# PR9021.net
KiCad netlist of a schematic drawn in EAGLE
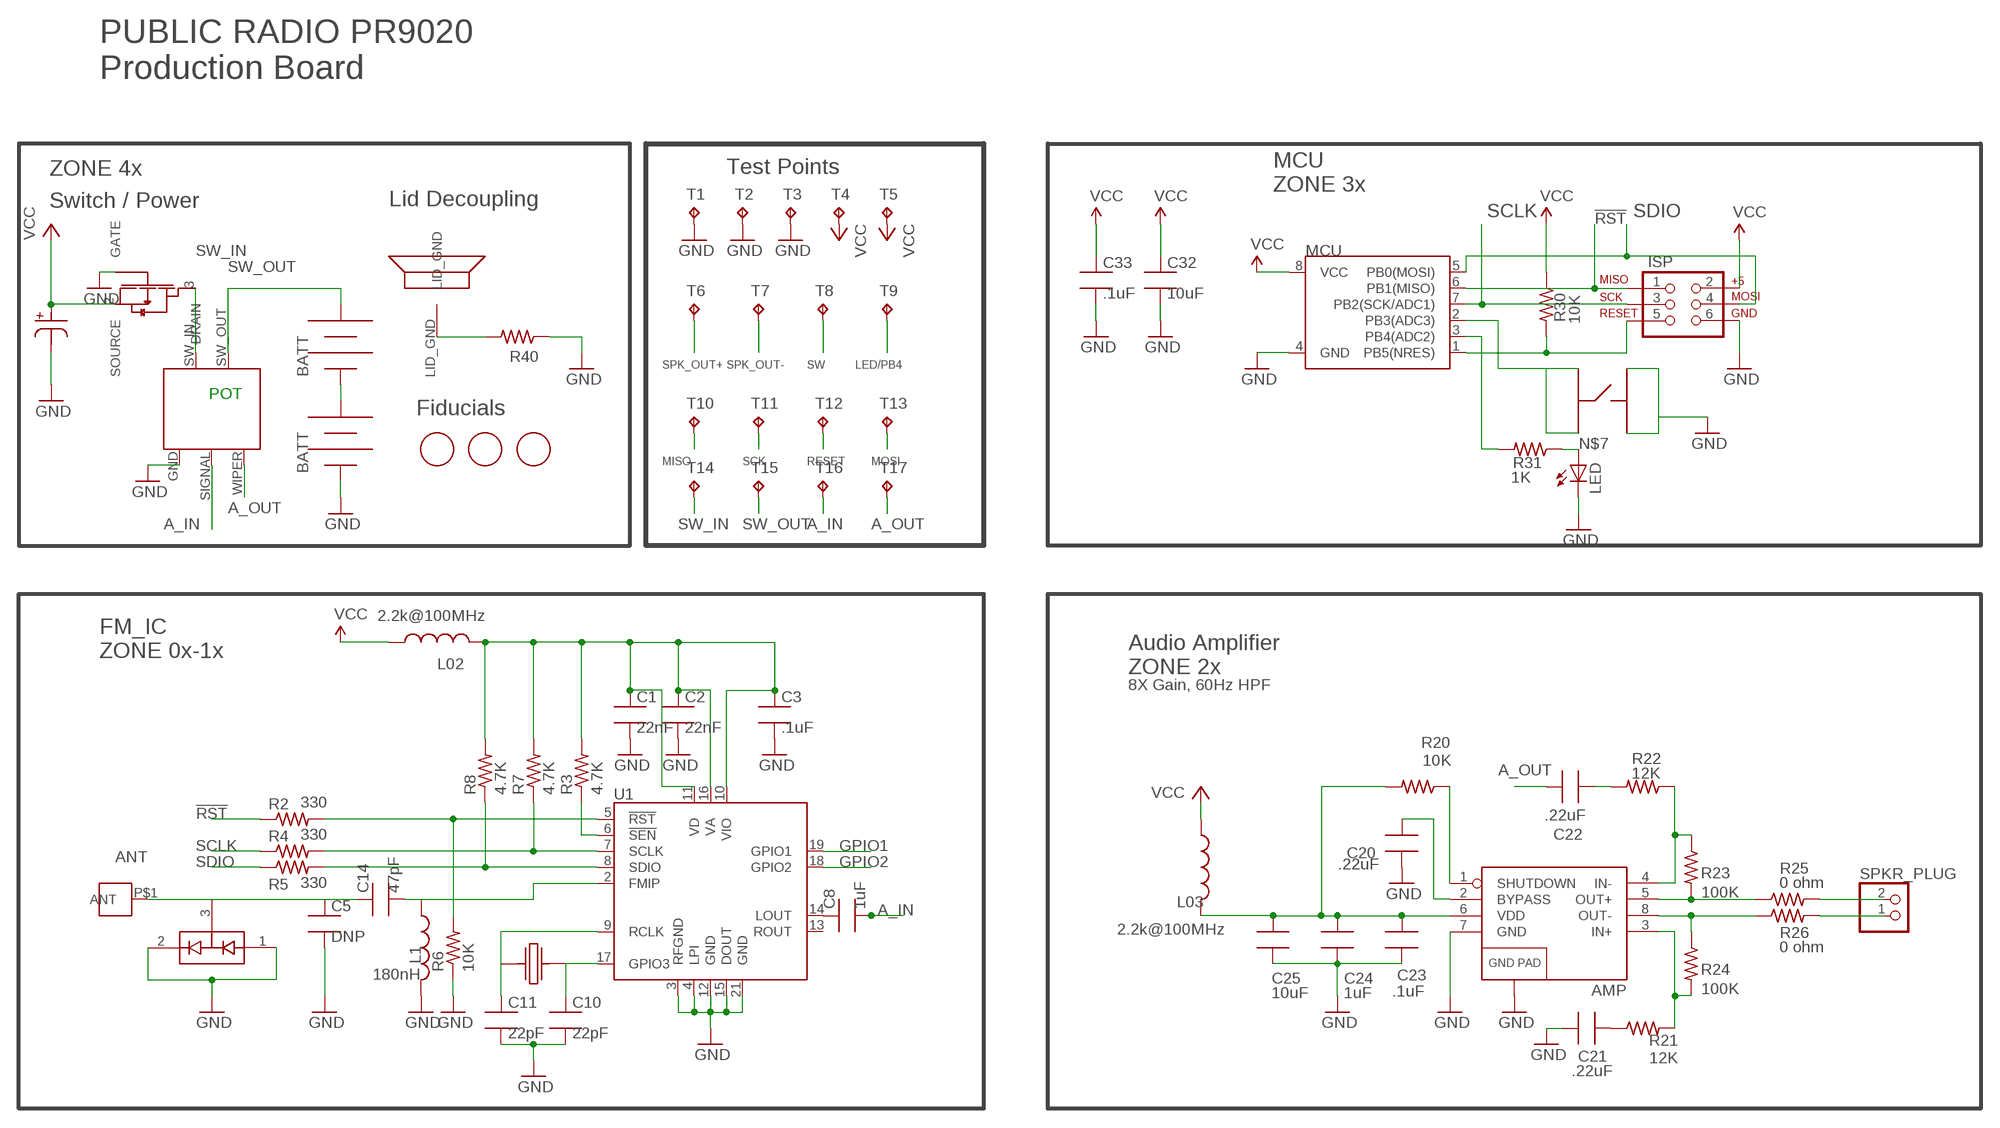
[diagram p0: schematic, sheet 1]

(export (version "E")
  (design (tool "Eeschema 10.0.6"))
  (components
    (comp (ref "AMP")
      (value "TPA6203A1")
      (footprint "eagle-import:8-MSOP")
      (libsource (lib "eagle-import") (part "TPA6203A1"))
    )
    (comp (ref "ANT_MOUNT")
      (value "DNP")
      (footprint "eagle-import:M3_BOLT_HOLE")
      (libsource (lib "eagle-import") (part "M3_SCREW_POST"))
    )
    (comp (ref "C1")
      (value "22nF")
      (footprint "eagle-import:0603_CPL")
      (fields
        (field (name "MFG_PN") "CL10B223KB8NNNC")
        (field (name "TOL") "10%")
        (field (name "VOLTAGE") "16V")
      )
      (libsource (lib "eagle-import") (part "C_SMT_0603_CPL"))
    )
    (comp (ref "C2")
      (value "22nF")
      (footprint "eagle-import:0603_CPL")
      (fields
        (field (name "MFG_PN") "CL10B223KB8NNNC")
        (field (name "TOL") "10%")
        (field (name "VOLTAGE") "16V")
      )
      (libsource (lib "eagle-import") (part "C_SMT_0603_CPL"))
    )
    (comp (ref "C3")
      (value ".1uF")
      (footprint "eagle-import:0603_CPL")
      (fields
        (field (name "MFG_PN") "CL10B104KB8SFNC")
        (field (name "TOL") "10%")
        (field (name "VOLTAGE") "16V")
      )
      (libsource (lib "eagle-import") (part "C_SMT_0603_CPL"))
    )
    (comp (ref "C5")
      (value "DNP")
      (footprint "eagle-import:0603_CPL")
      (fields (field (name "MFG_PN") "DNP") (field (name "TOL") "2%") (field (name "VOLTAGE") "50V"))
      (libsource (lib "eagle-import") (part "C_SMT_0603_CPL"))
    )
    (comp (ref "C8")
      (value "1uF")
      (footprint "eagle-import:0603_CPL")
      (fields
        (field (name "MFG_PN") "CL10B105KP8NNNC")
        (field (name "TOL") "10%")
        (field (name "VOLTAGE") "10V")
      )
      (libsource (lib "eagle-import") (part "C_SMT_0603_CPL"))
    )
    (comp (ref "C10")
      (value "22pF")
      (footprint "eagle-import:0603_CPL")
      (fields
        (field (name "MFG_PN") "C1608C0G1H220J080AA")
        (field (name "TOL") "5%")
        (field (name "VOLTAGE") "50V")
      )
      (libsource (lib "eagle-import") (part "C_SMT_0603_CPL"))
    )
    (comp (ref "C11")
      (value "22pF")
      (footprint "eagle-import:0603_CPL")
      (fields
        (field (name "MFG_PN") "C1608C0G1H220J080AA")
        (field (name "TOL") "5%")
        (field (name "VOLTAGE") "50V")
      )
      (libsource (lib "eagle-import") (part "C_SMT_0603_CPL"))
    )
    (comp (ref "C14")
      (value "47pF")
      (footprint "eagle-import:0603_CPL")
      (fields
        (field (name "MFG_PN") "CL10C470JB8NCNC")
        (field (name "TOL") "5%")
        (field (name "VOLTAGE") "50V")
      )
      (libsource (lib "eagle-import") (part "C_SMT_0603_CPL"))
    )
    (comp (ref "C20")
      (value ".22uF")
      (footprint "eagle-import:0603_CPL")
      (fields
        (field (name "MFG_PN") "C1608X7R1C224K080AC")
        (field (name "TOL") "10%")
        (field (name "VOLTAGE") "16V")
      )
      (libsource (lib "eagle-import") (part "C_SMT_0603_CPL"))
    )
    (comp (ref "C21")
      (value ".22uF")
      (footprint "eagle-import:0603_CPL")
      (fields
        (field (name "MFG_PN") "C1608X7R1C224K080AC")
        (field (name "TOL") "10%")
        (field (name "VOLTAGE") "16V")
      )
      (libsource (lib "eagle-import") (part "C_SMT_0603_CPL"))
    )
    (comp (ref "C22")
      (value ".22uF")
      (footprint "eagle-import:0603_CPL")
      (fields
        (field (name "MFG_PN") "C1608X7R1C224K080AC")
        (field (name "TOL") "10%")
        (field (name "VOLTAGE") "16V")
      )
      (libsource (lib "eagle-import") (part "C_SMT_0603_CPL"))
    )
    (comp (ref "C23")
      (value ".1uF")
      (footprint "eagle-import:0603_CPL")
      (fields
        (field (name "MFG_PN") "CL10B104KB8SFNC")
        (field (name "TOL") "10%")
        (field (name "VOLTAGE") "16V")
      )
      (libsource (lib "eagle-import") (part "C_SMT_0603_CPL"))
    )
    (comp (ref "C24")
      (value "1uF")
      (footprint "eagle-import:0603_CPL")
      (fields
        (field (name "MFG_PN") "CL10B105KP8NNNC")
        (field (name "TOL") "10%")
        (field (name "VOLTAGE") "10V")
      )
      (libsource (lib "eagle-import") (part "C_SMT_0603_CPL"))
    )
    (comp (ref "C25")
      (value "10uF")
      (footprint "eagle-import:0603_CPL")
      (fields
        (field (name "MFG_PN") "CL10A106MQ8NNNC")
        (field (name "TOL") "20%")
        (field (name "VOLTAGE") "6.3V")
      )
      (libsource (lib "eagle-import") (part "C_SMT_0603_CPL"))
    )
    (comp (ref "C32")
      (value "10uF")
      (footprint "eagle-import:0603_CPL")
      (fields
        (field (name "MFG_PN") "CL10A106MQ8NNNC")
        (field (name "TOL") "20%")
        (field (name "VOLTAGE") "6.3V")
      )
      (libsource (lib "eagle-import") (part "C_SMT_0603_CPL"))
    )
    (comp (ref "C33")
      (value ".1uF")
      (footprint "eagle-import:0603_CPL")
      (fields
        (field (name "MFG_PN") "CL10B104KB8SFNC")
        (field (name "TOL") "10%")
        (field (name "VOLTAGE") "16V")
      )
      (libsource (lib "eagle-import") (part "C_SMT_0603_CPL"))
    )
    (comp (ref "C40")
      (value "220uF")
      (footprint "eagle-import:NICHICON_UD_63")
      (fields (field (name "TOL") "20%") (field (name "VOLTAGE") "16V"))
      (libsource (lib "eagle-import") (part "NICHICON_SERIESUD"))
    )
    (comp (ref "D1")
      (value "BAV99")
      (footprint "eagle-import:SOT23_CPL")
      (fields (field (name "MFG_PN") "BAV99,215"))
      (libsource (lib "eagle-import") (part "BAV99"))
    )
    (comp (ref "FET1")
      (value "AO3435")
      (footprint "eagle-import:SOT23_CPL")
      (fields (field (name "MFG_PN") "AO3435"))
      (libsource (lib "eagle-import") (part "AO3435"))
    )
    (comp (ref "ISP")
      (value "AVR_SPI_PRG_6NS")
      (footprint "eagle-import:2X3-NS")
      (libsource (lib "eagle-import") (part "AVR_SPI_PRG_6NS"))
    )
    (comp (ref "JP5")
      (value "BK-92_MPD_AA_BATT_CLIP")
      (footprint "eagle-import:BK92_AA_BATT")
      (fields (field (name "MFG_PN") "2 of BK92 - supplied by CL Labs"))
      (libsource (lib "eagle-import") (part "BK-92_MPD_AA_BATT_CLIP"))
    )
    (comp (ref "JP6")
      (value "BK-92_MPD_AA_BATT_CLIP")
      (footprint "eagle-import:BK92_AA_BATT")
      (fields (field (name "MFG_PN") "2 of BK92 - supplied by CL Labs"))
      (libsource (lib "eagle-import") (part "BK-92_MPD_AA_BATT_CLIP"))
    )
    (comp (ref "L1")
      (value "180nH")
      (footprint "eagle-import:0805_ADAFRUIT")
      (fields
        (field (name "CURRENT") "400mA")
        (field (name "DCR") "640m")
        (field (name "MFG_PN") "AISC-0805-R18J-T")
        (field (name "TOL") "5%")
      )
      (libsource (lib "eagle-import") (part "L_SMT_0805_ADAFRUIT"))
    )
    (comp (ref "L02")
      (value "2.2k@100MHz")
      (footprint "eagle-import:0603_CPL")
      (fields
        (field (name "CURRENT") "150mA")
        (field (name "DCR") "2.3")
        (field (name "MFG_PN") "HZ0603A222R-10")
      )
      (libsource (lib "eagle-import") (part "L_SMT_0603_CPL"))
    )
    (comp (ref "L03")
      (value "2.2k@100MHz")
      (footprint "eagle-import:0603_CPL")
      (fields
        (field (name "CURRENT") "150mA")
        (field (name "DCR") "2.3")
        (field (name "MFG_PN") "HZ0603A222R-10")
      )
      (libsource (lib "eagle-import") (part "L_SMT_0603_CPL"))
    )
    (comp (ref "LED")
      (value "LEDCHIPLED_0805")
      (footprint "eagle-import:CHIPLED_0805")
      (libsource (lib "eagle-import") (part "LEDCHIPLED_0805"))
    )
    (comp (ref "MARK1")
      (value "FIDUCIAL")
      (footprint "eagle-import:FIDUCIAL_1MM")
      (libsource (lib "eagle-import") (part "FIDUCIAL"))
    )
    (comp (ref "MARK2")
      (value "FIDUCIAL")
      (footprint "eagle-import:FIDUCIAL_1MM")
      (libsource (lib "eagle-import") (part "FIDUCIAL"))
    )
    (comp (ref "MARK3")
      (value "FIDUCIAL")
      (footprint "eagle-import:FIDUCIAL_1MM")
      (libsource (lib "eagle-import") (part "FIDUCIAL"))
    )
    (comp (ref "MCU")
      (value "ATTINY45TINY45-20-SMT")
      (footprint "eagle-import:8-SOIC")
      (libsource (lib "eagle-import") (part "ATTINY45TINY45-20-SMT"))
    )
    (comp (ref "R1")
      (value "RV170SF_TAIWANA_POT_SW")
      (footprint "eagle-import:RV170SF_SW_POT")
      (fields (field (name "MFG_PN") "RV170SF-43-20F-A10K - supplied by CL Labs"))
      (libsource (lib "eagle-import") (part "RV170SF_TAIWANA_POT_SW"))
    )
    (comp (ref "R2")
      (value "330")
      (footprint "eagle-import:0603_CPL")
      (fields (field (name "MFG_PN") "MCR03ERTJ331") (field (name "POWER") "1/10W") (field (name "TOL") "5%"))
      (libsource (lib "eagle-import") (part "R_SMT_R0603_CPL"))
    )
    (comp (ref "R3")
      (value "4.7K")
      (footprint "eagle-import:0603_CPL")
      (fields
        (field (name "MFG_PN") "ERJ-3EKF4701V")
        (field (name "POWER") "1/10W")
        (field (name "TOL") "1%")
      )
      (libsource (lib "eagle-import") (part "R_SMT_R0603_CPL"))
    )
    (comp (ref "R4")
      (value "330")
      (footprint "eagle-import:0603_CPL")
      (fields (field (name "MFG_PN") "MCR03ERTJ331") (field (name "POWER") "1/10W") (field (name "TOL") "5%"))
      (libsource (lib "eagle-import") (part "R_SMT_R0603_CPL"))
    )
    (comp (ref "R5")
      (value "330")
      (footprint "eagle-import:0603_CPL")
      (fields (field (name "MFG_PN") "MCR03ERTJ331") (field (name "POWER") "1/10W") (field (name "TOL") "5%"))
      (libsource (lib "eagle-import") (part "R_SMT_R0603_CPL"))
    )
    (comp (ref "R6")
      (value "10K")
      (footprint "eagle-import:0603_CPL")
      (fields
        (field (name "MFG_PN") "ERJ-3GEYJ103V")
        (field (name "POWER") "1/10W")
        (field (name "TOL") "5%")
      )
      (libsource (lib "eagle-import") (part "R_SMT_R0603_CPL"))
    )
    (comp (ref "R7")
      (value "4.7K")
      (footprint "eagle-import:0603_CPL")
      (fields
        (field (name "MFG_PN") "ERJ-3EKF4701V")
        (field (name "POWER") "1/10W")
        (field (name "TOL") "1%")
      )
      (libsource (lib "eagle-import") (part "R_SMT_R0603_CPL"))
    )
    (comp (ref "R8")
      (value "4.7K")
      (footprint "eagle-import:0603_CPL")
      (fields
        (field (name "MFG_PN") "ERJ-3EKF4701V")
        (field (name "POWER") "1/10W")
        (field (name "TOL") "1%")
      )
      (libsource (lib "eagle-import") (part "R_SMT_R0603_CPL"))
    )
    (comp (ref "R20")
      (value "10K")
      (footprint "eagle-import:0603_CPL")
      (fields
        (field (name "MFG_PN") "ERJ-3GEYJ103V")
        (field (name "POWER") "1/10W")
        (field (name "TOL") "5%")
      )
      (libsource (lib "eagle-import") (part "R_SMT_R0603_CPL"))
    )
    (comp (ref "R21")
      (value "12K")
      (footprint "eagle-import:0603_CPL")
      (fields
        (field (name "MFG_PN") "RC0603FR-0712KL")
        (field (name "POWER") "1/10W")
        (field (name "TOL") "1%")
      )
      (libsource (lib "eagle-import") (part "R_SMT_R0603_CPL"))
    )
    (comp (ref "R22")
      (value "12K")
      (footprint "eagle-import:0603_CPL")
      (fields
        (field (name "MFG_PN") "RC0603FR-0712KL")
        (field (name "POWER") "1/10W")
        (field (name "TOL") "1%")
      )
      (libsource (lib "eagle-import") (part "R_SMT_R0603_CPL"))
    )
    (comp (ref "R23")
      (value "100K")
      (footprint "eagle-import:0603_CPL")
      (fields
        (field (name "MFG_PN") "ERJ-3EKF1003V")
        (field (name "POWER") "1/10W")
        (field (name "TOL") "1%")
      )
      (libsource (lib "eagle-import") (part "R_SMT_R0603_CPL"))
    )
    (comp (ref "R24")
      (value "100K")
      (footprint "eagle-import:0603_CPL")
      (fields
        (field (name "MFG_PN") "ERJ-3EKF1003V")
        (field (name "POWER") "1/10W")
        (field (name "TOL") "1%")
      )
      (libsource (lib "eagle-import") (part "R_SMT_R0603_CPL"))
    )
    (comp (ref "R25")
      (value "0 ohm")
      (footprint "eagle-import:0805_ADAFRUIT")
      (fields (field (name "MFG_PN") "ERJ-6GEY0R00V"))
      (libsource (lib "eagle-import") (part "R_SMT_0805_ADAFRUIT"))
    )
    (comp (ref "R26")
      (value "0 ohm")
      (footprint "eagle-import:0805_ADAFRUIT")
      (fields (field (name "MFG_PN") "ERJ-6GEY0R00V"))
      (libsource (lib "eagle-import") (part "R_SMT_0805_ADAFRUIT"))
    )
    (comp (ref "R30")
      (value "10K")
      (footprint "eagle-import:0603_CPL")
      (fields
        (field (name "MFG_PN") "ERJ-3GEYJ103V")
        (field (name "POWER") "1/10W")
        (field (name "TOL") "5%")
      )
      (libsource (lib "eagle-import") (part "R_SMT_R0603_CPL"))
    )
    (comp (ref "R31")
      (value "1K")
      (footprint "eagle-import:0603_CPL")
      (fields
        (field (name "MFG_PN") "ERJ-3EKF1001V")
        (field (name "POWER") "1/10W")
        (field (name "TOL") "1%")
      )
      (libsource (lib "eagle-import") (part "R_SMT_R0603_CPL"))
    )
    (comp (ref "R40")
      (value "R_SMT_R0603_CPL")
      (footprint "eagle-import:0603_CPL")
      (fields (field (name "MFG_PN") "ERJ-3GEY0R00V"))
      (libsource (lib "eagle-import") (part "R_SMT_R0603_CPL"))
    )
    (comp (ref "SPKR_PLACE")
      (value "DNP")
      (footprint "eagle-import:PR2023_SPKR_PLACE")
      (libsource (lib "eagle-import") (part "PR2023_SPKR"))
    )
    (comp (ref "SPKR_PLUG")
      (value "JST_2PIN-SMT-RA")
      (footprint "eagle-import:JST-B2B-PH-SM4-TB")
      (libsource (lib "eagle-import") (part "JST_2PIN-SMT-RA"))
    )
    (comp (ref "SW1")
      (value "C&K_PTS645")
      (footprint "eagle-import:C&K_PTS645_SMT")
      (libsource (lib "eagle-import") (part "C&K_PTS645"))
    )
    (comp (ref "T1")
      (value "TPTP20R")
      (footprint "eagle-import:TP20R")
      (libsource (lib "eagle-import") (part "TPTP20R"))
    )
    (comp (ref "T2")
      (value "TPTP20R")
      (footprint "eagle-import:TP20R")
      (libsource (lib "eagle-import") (part "TPTP20R"))
    )
    (comp (ref "T3")
      (value "TPTP20R")
      (footprint "eagle-import:TP20R")
      (libsource (lib "eagle-import") (part "TPTP20R"))
    )
    (comp (ref "T4")
      (value "TPTP20R")
      (footprint "eagle-import:TP20R")
      (libsource (lib "eagle-import") (part "TPTP20R"))
    )
    (comp (ref "T5")
      (value "TPTP20R")
      (footprint "eagle-import:TP20R")
      (libsource (lib "eagle-import") (part "TPTP20R"))
    )
    (comp (ref "T6")
      (value "TPTP20R")
      (footprint "eagle-import:TP20R")
      (libsource (lib "eagle-import") (part "TPTP20R"))
    )
    (comp (ref "T7")
      (value "TPTP20R")
      (footprint "eagle-import:TP20R")
      (libsource (lib "eagle-import") (part "TPTP20R"))
    )
    (comp (ref "T8")
      (value "TPTP20R")
      (footprint "eagle-import:TP20R")
      (libsource (lib "eagle-import") (part "TPTP20R"))
    )
    (comp (ref "T9")
      (value "TPTP20R")
      (footprint "eagle-import:TP20R")
      (libsource (lib "eagle-import") (part "TPTP20R"))
    )
    (comp (ref "T10")
      (value "TPTP20R")
      (footprint "eagle-import:TP20R")
      (libsource (lib "eagle-import") (part "TPTP20R"))
    )
    (comp (ref "T11")
      (value "TPTP20R")
      (footprint "eagle-import:TP20R")
      (libsource (lib "eagle-import") (part "TPTP20R"))
    )
    (comp (ref "T12")
      (value "TPTP20R")
      (footprint "eagle-import:TP20R")
      (libsource (lib "eagle-import") (part "TPTP20R"))
    )
    (comp (ref "T13")
      (value "TPTP20R")
      (footprint "eagle-import:TP20R")
      (libsource (lib "eagle-import") (part "TPTP20R"))
    )
    (comp (ref "T14")
      (value "TPTP20R")
      (footprint "eagle-import:TP20R")
      (libsource (lib "eagle-import") (part "TPTP20R"))
    )
    (comp (ref "T15")
      (value "TPTP20R")
      (footprint "eagle-import:TP20R")
      (libsource (lib "eagle-import") (part "TPTP20R"))
    )
    (comp (ref "T16")
      (value "TPTP20R")
      (footprint "eagle-import:TP20R")
      (libsource (lib "eagle-import") (part "TPTP20R"))
    )
    (comp (ref "T17")
      (value "TPTP20R")
      (footprint "eagle-import:TP20R")
      (libsource (lib "eagle-import") (part "TPTP20R"))
    )
    (comp (ref "U1")
      (value "SI4702-C19-GMR")
      (footprint "eagle-import:SI470X_20_QFN")
      (fields (field (name "MFG_PN") "Si4702 C19 GM - supplied by CL Labs"))
      (libsource (lib "eagle-import") (part "SI4702-C19-GMR"))
    )
    (comp (ref "X1")
      (value "ABS25XTAL")
      (footprint "eagle-import:4-SOJ")
      (libsource (lib "eagle-import") (part "ABS25XTAL"))
    )
  )
  (nets
    (net (code "1") (name "/ANT") (class "Default")
      (node (ref "ANT_MOUNT") (pin "P$1") (pinfunction "ANT_P$1") (pintype "bidirectional"))
      (node (ref "C14") (pin "1") (pinfunction "1_1") (pintype "passive"))
      (node (ref "C5") (pin "1") (pinfunction "1_1") (pintype "passive"))
      (node (ref "D1") (pin "3") (pinfunction "COM_3") (pintype "bidirectional"))
    )
    (net (code "2") (name "/A_IN") (class "Default")
      (node (ref "C8") (pin "2") (pinfunction "2_2") (pintype "passive"))
      (node (ref "R1") (pin "SIGNAL") (pinfunction "SIGNAL_SIGNAL") (pintype "bidirectional"))
      (node (ref "T16") (pin "TP") (pinfunction "TP_TP") (pintype "input"))
    )
    (net (code "3") (name "/A_OUT") (class "Default")
      (node (ref "C22") (pin "2") (pinfunction "2_2") (pintype "passive"))
      (node (ref "R1") (pin "WIPER") (pinfunction "WIPER_WIPER") (pintype "bidirectional"))
      (node (ref "T17") (pin "TP") (pinfunction "TP_TP") (pintype "input"))
    )
    (net (code "4") (name "/GPIO1") (class "Default")
      (node (ref "U1") (pin "19") (pinfunction "GPIO1_19") (pintype "bidirectional"))
    )
    (net (code "5") (name "/GPIO2") (class "Default")
      (node (ref "U1") (pin "18") (pinfunction "GPIO2_18") (pintype "bidirectional"))
    )
    (net (code "6") (name "/LED{slash}PB4") (class "Default")
      (node (ref "MCU") (pin "3") (pinfunction "PB4(ADC2)_3") (pintype "bidirectional"))
      (node (ref "R31") (pin "2") (pinfunction "2_2") (pintype "passive"))
      (node (ref "T9") (pin "TP") (pinfunction "TP_TP") (pintype "input"))
    )
    (net (code "7") (name "/N$7") (class "Default")
      (node (ref "LED") (pin "A") (pinfunction "A_A") (pintype "passive"))
      (node (ref "R31") (pin "1") (pinfunction "1_1") (pintype "passive"))
    )
    (net (code "8") (name "/RESET") (class "Default")
      (node (ref "ISP") (pin "5") (pinfunction "5_5") (pintype "passive"))
      (node (ref "MCU") (pin "1") (pinfunction "PB5(NRES)_1") (pintype "bidirectional"))
      (node (ref "R30") (pin "2") (pinfunction "2_2") (pintype "passive"))
      (node (ref "T12") (pin "TP") (pinfunction "TP_TP") (pintype "input"))
    )
    (net (code "9") (name "/SCLK") (class "Default")
      (node (ref "ISP") (pin "3") (pinfunction "3_3") (pintype "passive"))
      (node (ref "MCU") (pin "7") (pinfunction "PB2(SCK/ADC1)_7") (pintype "bidirectional"))
      (node (ref "R4") (pin "1") (pinfunction "1_1") (pintype "passive"))
      (node (ref "T11") (pin "TP") (pinfunction "TP_TP") (pintype "input"))
    )
    (net (code "10") (name "/SDIO") (class "Default")
      (node (ref "ISP") (pin "4") (pinfunction "4_4") (pintype "passive"))
      (node (ref "MCU") (pin "5") (pinfunction "PB0(MOSI)_5") (pintype "bidirectional"))
      (node (ref "R5") (pin "1") (pinfunction "1_1") (pintype "passive"))
      (node (ref "T13") (pin "TP") (pinfunction "TP_TP") (pintype "input"))
    )
    (net (code "11") (name "/SPK_OUT+") (class "Default")
      (node (ref "R25") (pin "2") (pinfunction "2_2") (pintype "passive"))
      (node (ref "SPKR_PLUG") (pin "2") (pinfunction "1_2") (pintype "passive"))
      (node (ref "T6") (pin "TP") (pinfunction "TP_TP") (pintype "input"))
    )
    (net (code "12") (name "/SPK_OUT-") (class "Default")
      (node (ref "R26") (pin "2") (pinfunction "2_2") (pintype "passive"))
      (node (ref "SPKR_PLUG") (pin "1") (pinfunction "2_1") (pintype "passive"))
      (node (ref "T7") (pin "TP") (pinfunction "TP_TP") (pintype "input"))
    )
    (net (code "13") (name "/SW") (class "Default")
      (node (ref "MCU") (pin "2") (pinfunction "PB3(ADC3)_2") (pintype "bidirectional"))
      (node (ref "SW1") (pin "P$3") (pinfunction "P$3_P$3") (pintype "bidirectional"))
      (node (ref "SW1") (pin "P$4") (pinfunction "P$4_P$4") (pintype "bidirectional"))
      (node (ref "T8") (pin "TP") (pinfunction "TP_TP") (pintype "input"))
    )
    (net (code "14") (name "/SW_IN") (class "Default")
      (node (ref "FET1") (pin "3") (pinfunction "DRAIN_3") (pintype "bidirectional"))
      (node (ref "R1") (pin "SW_IN") (pinfunction "SW_IN_SW_IN") (pintype "bidirectional"))
      (node (ref "T14") (pin "TP") (pinfunction "TP_TP") (pintype "input"))
    )
    (net (code "15") (name "/SW_OUT") (class "Default")
      (node (ref "JP5") (pin "POS") (pinfunction "POS_POS") (pintype "bidirectional"))
      (node (ref "JP5") (pin "POS@2") (pinfunction "POS_POS@2") (pintype "bidirectional"))
      (node (ref "R1") (pin "SW_OUT") (pinfunction "SW_OUT_SW_OUT") (pintype "bidirectional"))
      (node (ref "T15") (pin "TP") (pinfunction "TP_TP") (pintype "input"))
    )
    (net (code "16") (name "/~{RST}") (class "Default")
      (node (ref "ISP") (pin "1") (pinfunction "1_1") (pintype "passive"))
      (node (ref "MCU") (pin "6") (pinfunction "PB1(MISO)_6") (pintype "bidirectional"))
      (node (ref "R2") (pin "1") (pinfunction "1_1") (pintype "passive"))
      (node (ref "T10") (pin "TP") (pinfunction "TP_TP") (pintype "input"))
    )
    (net (code "17") (name "GND") (class "Default")
      (node (ref "AMP") (pin "7") (pinfunction "GND_7") (pintype "power_in"))
      (node (ref "AMP") (pin "9") (pinfunction "GND_9") (pintype "power_in"))
      (node (ref "C1") (pin "2") (pinfunction "2_2") (pintype "passive"))
      (node (ref "C10") (pin "2") (pinfunction "2_2") (pintype "passive"))
      (node (ref "C11") (pin "2") (pinfunction "2_2") (pintype "passive"))
      (node (ref "C2") (pin "2") (pinfunction "2_2") (pintype "passive"))
      (node (ref "C20") (pin "1") (pinfunction "1_1") (pintype "passive"))
      (node (ref "C21") (pin "1") (pinfunction "1_1") (pintype "passive"))
      (node (ref "C23") (pin "2") (pinfunction "2_2") (pintype "passive"))
      (node (ref "C24") (pin "2") (pinfunction "2_2") (pintype "passive"))
      (node (ref "C25") (pin "2") (pinfunction "2_2") (pintype "passive"))
      (node (ref "C3") (pin "2") (pinfunction "2_2") (pintype "passive"))
      (node (ref "C32") (pin "2") (pinfunction "2_2") (pintype "passive"))
      (node (ref "C33") (pin "2") (pinfunction "2_2") (pintype "passive"))
      (node (ref "C40") (pin "P$2") (pinfunction "P$2_P$2") (pintype "bidirectional"))
      (node (ref "C5") (pin "2") (pinfunction "2_2") (pintype "passive"))
      (node (ref "D1") (pin "1") (pinfunction "A1_1") (pintype "bidirectional"))
      (node (ref "D1") (pin "2") (pinfunction "C2_2") (pintype "bidirectional"))
      (node (ref "FET1") (pin "1") (pinfunction "GATE_1") (pintype "bidirectional"))
      (node (ref "ISP") (pin "6") (pinfunction "6_6") (pintype "passive"))
      (node (ref "JP6") (pin "NEG") (pinfunction "NEG_NEG") (pintype "bidirectional"))
      (node (ref "JP6") (pin "NEG@2") (pinfunction "NEG_NEG@2") (pintype "bidirectional"))
      (node (ref "L1") (pin "2") (pinfunction "2_2") (pintype "passive"))
      (node (ref "LED") (pin "C") (pinfunction "C_C") (pintype "passive"))
      (node (ref "MCU") (pin "4") (pinfunction "GND_4") (pintype "bidirectional"))
      (node (ref "R1") (pin "GND") (pinfunction "GND_GND") (pintype "bidirectional"))
      (node (ref "R40") (pin "1") (pinfunction "1_1") (pintype "passive"))
      (node (ref "R6") (pin "1") (pinfunction "1_1") (pintype "passive"))
      (node (ref "SW1") (pin "P$1") (pinfunction "P$1_P$1") (pintype "bidirectional"))
      (node (ref "SW1") (pin "P$2") (pinfunction "P$2_P$2") (pintype "bidirectional"))
      (node (ref "T1") (pin "TP") (pinfunction "TP_TP") (pintype "input"))
      (node (ref "T2") (pin "TP") (pinfunction "TP_TP") (pintype "input"))
      (node (ref "T3") (pin "TP") (pinfunction "TP_TP") (pintype "input"))
      (node (ref "U1") (pin "12") (pinfunction "GND_12") (pintype "bidirectional"))
      (node (ref "U1") (pin "15") (pinfunction "DOUT_15") (pintype "bidirectional"))
      (node (ref "U1") (pin "21") (pinfunction "GND_21") (pintype "bidirectional"))
      (node (ref "U1") (pin "3") (pinfunction "RFGND_3") (pintype "bidirectional"))
      (node (ref "U1") (pin "4") (pinfunction "LPI_4") (pintype "bidirectional"))
    )
    (net (code "18") (name "Net-(AMP-BYPASS)") (class "Default")
      (node (ref "AMP") (pin "2") (pinfunction "BYPASS_2") (pintype "bidirectional"))
      (node (ref "C20") (pin "2") (pinfunction "2_2") (pintype "passive"))
    )
    (net (code "19") (name "Net-(AMP-IN+)") (class "Default")
      (node (ref "AMP") (pin "3") (pinfunction "IN+_3") (pintype "bidirectional"))
      (node (ref "R21") (pin "2") (pinfunction "2_2") (pintype "passive"))
      (node (ref "R24") (pin "2") (pinfunction "2_2") (pintype "passive"))
    )
    (net (code "20") (name "Net-(AMP-IN-)") (class "Default")
      (node (ref "AMP") (pin "4") (pinfunction "IN-_4") (pintype "bidirectional"))
      (node (ref "R22") (pin "1") (pinfunction "1_1") (pintype "passive"))
      (node (ref "R23") (pin "1") (pinfunction "1_1") (pintype "passive"))
    )
    (net (code "21") (name "Net-(AMP-OUT+)") (class "Default")
      (node (ref "AMP") (pin "5") (pinfunction "OUT+_5") (pintype "bidirectional"))
      (node (ref "R23") (pin "2") (pinfunction "2_2") (pintype "passive"))
      (node (ref "R25") (pin "1") (pinfunction "1_1") (pintype "passive"))
    )
    (net (code "22") (name "Net-(AMP-OUT-)") (class "Default")
      (node (ref "AMP") (pin "8") (pinfunction "OUT-_8") (pintype "bidirectional"))
      (node (ref "R24") (pin "1") (pinfunction "1_1") (pintype "passive"))
      (node (ref "R26") (pin "1") (pinfunction "1_1") (pintype "passive"))
    )
    (net (code "23") (name "Net-(AMP-SHUTDOWN)") (class "Default")
      (node (ref "AMP") (pin "1") (pinfunction "SHUTDOWN_1") (pintype "input"))
      (node (ref "R20") (pin "1") (pinfunction "1_1") (pintype "passive"))
    )
    (net (code "24") (name "Net-(AMP-VDD)") (class "Default")
      (node (ref "AMP") (pin "6") (pinfunction "VDD_6") (pintype "power_in"))
      (node (ref "C23") (pin "1") (pinfunction "1_1") (pintype "passive"))
      (node (ref "C24") (pin "1") (pinfunction "1_1") (pintype "passive"))
      (node (ref "C25") (pin "1") (pinfunction "1_1") (pintype "passive"))
      (node (ref "L03") (pin "2") (pinfunction "2_2") (pintype "passive"))
      (node (ref "R20") (pin "2") (pinfunction "2_2") (pintype "passive"))
    )
    (net (code "25") (name "Net-(C21-Pad2)") (class "Default")
      (node (ref "C21") (pin "2") (pinfunction "2_2") (pintype "passive"))
      (node (ref "R21") (pin "1") (pinfunction "1_1") (pintype "passive"))
    )
    (net (code "26") (name "Net-(C22-Pad1)") (class "Default")
      (node (ref "C22") (pin "1") (pinfunction "1_1") (pintype "passive"))
      (node (ref "R22") (pin "2") (pinfunction "2_2") (pintype "passive"))
    )
    (net (code "27") (name "Net-(JP5-NEG-PadNEG@2)") (class "Default")
      (node (ref "JP5") (pin "NEG") (pinfunction "NEG_NEG") (pintype "bidirectional"))
      (node (ref "JP5") (pin "NEG@2") (pinfunction "NEG_NEG@2") (pintype "bidirectional"))
      (node (ref "JP6") (pin "POS") (pinfunction "POS_POS") (pintype "bidirectional"))
      (node (ref "JP6") (pin "POS@2") (pinfunction "POS_POS@2") (pintype "bidirectional"))
    )
    (net (code "28") (name "Net-(R40-Pad2)") (class "Default")
      (node (ref "R40") (pin "2") (pinfunction "2_2") (pintype "passive"))
      (node (ref "SPKR_PLACE") (pin "LID_GND") (pinfunction "LID_GND_LID_GND") (pintype "bidirectional"))
    )
    (net (code "29") (name "Net-(U1-FMIP)") (class "Default")
      (node (ref "C14") (pin "2") (pinfunction "2_2") (pintype "passive"))
      (node (ref "L1") (pin "1") (pinfunction "1_1") (pintype "passive"))
      (node (ref "U1") (pin "2") (pinfunction "FMIP_2") (pintype "bidirectional"))
    )
    (net (code "30") (name "Net-(U1-GPIO3)") (class "Default")
      (node (ref "C10") (pin "1") (pinfunction "1_1") (pintype "passive"))
      (node (ref "U1") (pin "17") (pinfunction "GPIO3_17") (pintype "bidirectional"))
      (node (ref "X1") (pin "P$4") (pinfunction "P$4_P$4") (pintype "bidirectional"))
    )
    (net (code "31") (name "Net-(U1-LOUT)") (class "Default")
      (node (ref "C8") (pin "1") (pinfunction "1_1") (pintype "passive"))
      (node (ref "U1") (pin "14") (pinfunction "LOUT_14") (pintype "bidirectional"))
    )
    (net (code "32") (name "Net-(U1-RCLK)") (class "Default")
      (node (ref "C11") (pin "1") (pinfunction "1_1") (pintype "passive"))
      (node (ref "U1") (pin "9") (pinfunction "RCLK_9") (pintype "bidirectional"))
      (node (ref "X1") (pin "P$1") (pinfunction "P$1_P$1") (pintype "bidirectional"))
    )
    (net (code "33") (name "Net-(U1-SCLK)") (class "Default")
      (node (ref "R4") (pin "2") (pinfunction "2_2") (pintype "passive"))
      (node (ref "R7") (pin "1") (pinfunction "1_1") (pintype "passive"))
      (node (ref "U1") (pin "7") (pinfunction "SCLK_7") (pintype "bidirectional"))
    )
    (net (code "34") (name "Net-(U1-SDIO)") (class "Default")
      (node (ref "R5") (pin "2") (pinfunction "2_2") (pintype "passive"))
      (node (ref "R8") (pin "1") (pinfunction "1_1") (pintype "passive"))
      (node (ref "U1") (pin "8") (pinfunction "SDIO_8") (pintype "bidirectional"))
    )
    (net (code "35") (name "Net-(U1-VA)") (class "Default")
      (node (ref "C1") (pin "1") (pinfunction "1_1") (pintype "passive"))
      (node (ref "C2") (pin "1") (pinfunction "1_1") (pintype "passive"))
      (node (ref "C3") (pin "1") (pinfunction "1_1") (pintype "passive"))
      (node (ref "L02") (pin "2") (pinfunction "2_2") (pintype "passive"))
      (node (ref "R3") (pin "2") (pinfunction "2_2") (pintype "passive"))
      (node (ref "R7") (pin "2") (pinfunction "2_2") (pintype "passive"))
      (node (ref "R8") (pin "2") (pinfunction "2_2") (pintype "passive"))
      (node (ref "U1") (pin "10") (pinfunction "VIO_10") (pintype "bidirectional"))
      (node (ref "U1") (pin "11") (pinfunction "VD_11") (pintype "bidirectional"))
      (node (ref "U1") (pin "16") (pinfunction "VA_16") (pintype "bidirectional"))
    )
    (net (code "36") (name "Net-(U1-~{RST})") (class "Default")
      (node (ref "R2") (pin "2") (pinfunction "2_2") (pintype "passive"))
      (node (ref "R6") (pin "2") (pinfunction "2_2") (pintype "passive"))
      (node (ref "U1") (pin "5") (pinfunction "~{RST}_5") (pintype "bidirectional"))
    )
    (net (code "37") (name "Net-(U1-~{SEN})") (class "Default")
      (node (ref "R3") (pin "1") (pinfunction "1_1") (pintype "passive"))
      (node (ref "U1") (pin "6") (pinfunction "~{SEN}_6") (pintype "bidirectional"))
    )
    (net (code "38") (name "VCC") (class "Default")
      (node (ref "C32") (pin "1") (pinfunction "1_1") (pintype "passive"))
      (node (ref "C33") (pin "1") (pinfunction "1_1") (pintype "passive"))
      (node (ref "C40") (pin "P$1") (pinfunction "P$1_P$1") (pintype "bidirectional"))
      (node (ref "FET1") (pin "2") (pinfunction "SOURCE_2") (pintype "bidirectional"))
      (node (ref "ISP") (pin "2") (pinfunction "2_2") (pintype "passive"))
      (node (ref "L02") (pin "1") (pinfunction "1_1") (pintype "passive"))
      (node (ref "L03") (pin "1") (pinfunction "1_1") (pintype "passive"))
      (node (ref "MCU") (pin "8") (pinfunction "VCC_8") (pintype "bidirectional"))
      (node (ref "R30") (pin "1") (pinfunction "1_1") (pintype "passive"))
      (node (ref "T4") (pin "TP") (pinfunction "TP_TP") (pintype "input"))
      (node (ref "T5") (pin "TP") (pinfunction "TP_TP") (pintype "input"))
    )
    (net (code "39") (name "unconnected-(U1-ROUT-Pad13)") (class "Default")
      (node (ref "U1") (pin "13") (pinfunction "ROUT_13") (pintype "bidirectional"))
    )
  )
)
